# LEDnecklaceW.net
KiCad netlist of a schematic drawn in EAGLE
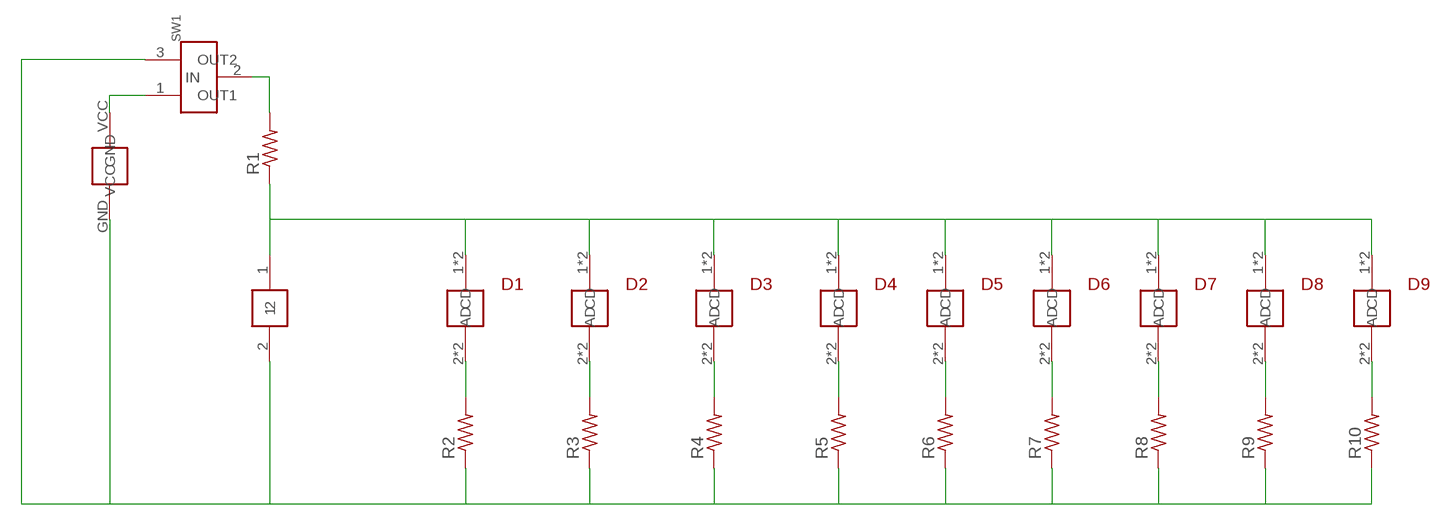
[diagram p0: schematic, sheet 1]

(export (version "E")
  (design (tool "Eeschema 10.0.6"))
  (components
    (comp (ref "D1")
      (value "SZA05A0A")
      (footprint "eagle-import:SZA05A0A")
      (libsource (lib "eagle-import") (part "SZA05A0A"))
    )
    (comp (ref "D2")
      (value "SZA05A0A")
      (footprint "eagle-import:SZA05A0A")
      (libsource (lib "eagle-import") (part "SZA05A0A"))
    )
    (comp (ref "D3")
      (value "SZA05A0A")
      (footprint "eagle-import:SZA05A0A")
      (libsource (lib "eagle-import") (part "SZA05A0A"))
    )
    (comp (ref "D4")
      (value "SZA05A0A")
      (footprint "eagle-import:SZA05A0A")
      (libsource (lib "eagle-import") (part "SZA05A0A"))
    )
    (comp (ref "D5")
      (value "SZA05A0A")
      (footprint "eagle-import:SZA05A0A")
      (libsource (lib "eagle-import") (part "SZA05A0A"))
    )
    (comp (ref "D6")
      (value "SZA05A0A")
      (footprint "eagle-import:SZA05A0A")
      (libsource (lib "eagle-import") (part "SZA05A0A"))
    )
    (comp (ref "D7")
      (value "SZA05A0A")
      (footprint "eagle-import:SZA05A0A")
      (libsource (lib "eagle-import") (part "SZA05A0A"))
    )
    (comp (ref "D8")
      (value "SZA05A0A")
      (footprint "eagle-import:SZA05A0A")
      (libsource (lib "eagle-import") (part "SZA05A0A"))
    )
    (comp (ref "D9")
      (value "SZA05A0A")
      (footprint "eagle-import:SZA05A0A")
      (libsource (lib "eagle-import") (part "SZA05A0A"))
    )
    (comp (ref "P1")
      (value "BU2032SM-BT-GCT")
      (footprint "eagle-import:SMD_BATT_HOLDER_2032")
      (libsource (lib "eagle-import") (part "BU2032SM-BT-GCT"))
    )
    (comp (ref "PC1")
      (value "PDV-P8101")
      (footprint "eagle-import:PHOTOCELL_CERAMIC")
      (libsource (lib "eagle-import") (part "PDV-P8101"))
    )
    (comp (ref "R1")
      (value "R-US_R0603")
      (footprint "eagle-import:R0603")
      (libsource (lib "eagle-import") (part "R-US_R0603"))
    )
    (comp (ref "R2")
      (value "R-US_R0603")
      (footprint "eagle-import:R0603")
      (libsource (lib "eagle-import") (part "R-US_R0603"))
    )
    (comp (ref "R3")
      (value "R-US_R0603")
      (footprint "eagle-import:R0603")
      (libsource (lib "eagle-import") (part "R-US_R0603"))
    )
    (comp (ref "R4")
      (value "R-US_R0603")
      (footprint "eagle-import:R0603")
      (libsource (lib "eagle-import") (part "R-US_R0603"))
    )
    (comp (ref "R5")
      (value "R-US_R0603")
      (footprint "eagle-import:R0603")
      (libsource (lib "eagle-import") (part "R-US_R0603"))
    )
    (comp (ref "R6")
      (value "R-US_R0603")
      (footprint "eagle-import:R0603")
      (libsource (lib "eagle-import") (part "R-US_R0603"))
    )
    (comp (ref "R7")
      (value "R-US_R0603")
      (footprint "eagle-import:R0603")
      (libsource (lib "eagle-import") (part "R-US_R0603"))
    )
    (comp (ref "R8")
      (value "R-US_R0603")
      (footprint "eagle-import:R0603")
      (libsource (lib "eagle-import") (part "R-US_R0603"))
    )
    (comp (ref "R9")
      (value "R-US_R0603")
      (footprint "eagle-import:R0603")
      (libsource (lib "eagle-import") (part "R-US_R0603"))
    )
    (comp (ref "R10")
      (value "R-US_R0603")
      (footprint "eagle-import:R0603")
      (libsource (lib "eagle-import") (part "R-US_R0603"))
    )
    (comp (ref "SW1")
      (value "PCM12SMTR")
      (footprint "eagle-import:PCM12SMTR")
      (libsource (lib "eagle-import") (part "PCM12SMTR"))
    )
  )
  (nets
    (net (code "1") (name "Net-(D1-AD-Pad1)") (class "Default")
      (node (ref "D1") (pin "1") (pinfunction "AD_1") (pintype "bidirectional"))
      (node (ref "D1") (pin "11") (pinfunction "AD_11") (pintype "bidirectional"))
      (node (ref "D2") (pin "1") (pinfunction "AD_1") (pintype "bidirectional"))
      (node (ref "D2") (pin "11") (pinfunction "AD_11") (pintype "bidirectional"))
      (node (ref "D3") (pin "1") (pinfunction "AD_1") (pintype "bidirectional"))
      (node (ref "D3") (pin "11") (pinfunction "AD_11") (pintype "bidirectional"))
      (node (ref "D4") (pin "1") (pinfunction "AD_1") (pintype "bidirectional"))
      (node (ref "D4") (pin "11") (pinfunction "AD_11") (pintype "bidirectional"))
      (node (ref "D5") (pin "1") (pinfunction "AD_1") (pintype "bidirectional"))
      (node (ref "D5") (pin "11") (pinfunction "AD_11") (pintype "bidirectional"))
      (node (ref "D6") (pin "1") (pinfunction "AD_1") (pintype "bidirectional"))
      (node (ref "D6") (pin "11") (pinfunction "AD_11") (pintype "bidirectional"))
      (node (ref "D7") (pin "1") (pinfunction "AD_1") (pintype "bidirectional"))
      (node (ref "D7") (pin "11") (pinfunction "AD_11") (pintype "bidirectional"))
      (node (ref "D8") (pin "1") (pinfunction "AD_1") (pintype "bidirectional"))
      (node (ref "D8") (pin "11") (pinfunction "AD_11") (pintype "bidirectional"))
      (node (ref "D9") (pin "1") (pinfunction "AD_1") (pintype "bidirectional"))
      (node (ref "D9") (pin "11") (pinfunction "AD_11") (pintype "bidirectional"))
      (node (ref "PC1") (pin "1") (pinfunction "1_1") (pintype "bidirectional"))
      (node (ref "R1") (pin "1") (pinfunction "1_1") (pintype "passive"))
    )
    (net (code "2") (name "Net-(D1-CD-Pad12)") (class "Default")
      (node (ref "D1") (pin "12") (pinfunction "CD_12") (pintype "bidirectional"))
      (node (ref "D1") (pin "2") (pinfunction "CD_2") (pintype "bidirectional"))
      (node (ref "R2") (pin "2") (pinfunction "2_2") (pintype "passive"))
    )
    (net (code "3") (name "Net-(D2-CD-Pad12)") (class "Default")
      (node (ref "D2") (pin "12") (pinfunction "CD_12") (pintype "bidirectional"))
      (node (ref "D2") (pin "2") (pinfunction "CD_2") (pintype "bidirectional"))
      (node (ref "R3") (pin "2") (pinfunction "2_2") (pintype "passive"))
    )
    (net (code "4") (name "Net-(D3-CD-Pad12)") (class "Default")
      (node (ref "D3") (pin "12") (pinfunction "CD_12") (pintype "bidirectional"))
      (node (ref "D3") (pin "2") (pinfunction "CD_2") (pintype "bidirectional"))
      (node (ref "R4") (pin "2") (pinfunction "2_2") (pintype "passive"))
    )
    (net (code "5") (name "Net-(D4-CD-Pad12)") (class "Default")
      (node (ref "D4") (pin "12") (pinfunction "CD_12") (pintype "bidirectional"))
      (node (ref "D4") (pin "2") (pinfunction "CD_2") (pintype "bidirectional"))
      (node (ref "R5") (pin "2") (pinfunction "2_2") (pintype "passive"))
    )
    (net (code "6") (name "Net-(D5-CD-Pad12)") (class "Default")
      (node (ref "D5") (pin "12") (pinfunction "CD_12") (pintype "bidirectional"))
      (node (ref "D5") (pin "2") (pinfunction "CD_2") (pintype "bidirectional"))
      (node (ref "R6") (pin "2") (pinfunction "2_2") (pintype "passive"))
    )
    (net (code "7") (name "Net-(D6-CD-Pad12)") (class "Default")
      (node (ref "D6") (pin "12") (pinfunction "CD_12") (pintype "bidirectional"))
      (node (ref "D6") (pin "2") (pinfunction "CD_2") (pintype "bidirectional"))
      (node (ref "R7") (pin "2") (pinfunction "2_2") (pintype "passive"))
    )
    (net (code "8") (name "Net-(D7-CD-Pad12)") (class "Default")
      (node (ref "D7") (pin "12") (pinfunction "CD_12") (pintype "bidirectional"))
      (node (ref "D7") (pin "2") (pinfunction "CD_2") (pintype "bidirectional"))
      (node (ref "R8") (pin "2") (pinfunction "2_2") (pintype "passive"))
    )
    (net (code "9") (name "Net-(D8-CD-Pad12)") (class "Default")
      (node (ref "D8") (pin "12") (pinfunction "CD_12") (pintype "bidirectional"))
      (node (ref "D8") (pin "2") (pinfunction "CD_2") (pintype "bidirectional"))
      (node (ref "R9") (pin "2") (pinfunction "2_2") (pintype "passive"))
    )
    (net (code "10") (name "Net-(D9-CD-Pad12)") (class "Default")
      (node (ref "D9") (pin "12") (pinfunction "CD_12") (pintype "bidirectional"))
      (node (ref "D9") (pin "2") (pinfunction "CD_2") (pintype "bidirectional"))
      (node (ref "R10") (pin "2") (pinfunction "2_2") (pintype "passive"))
    )
    (net (code "11") (name "Net-(SW1-IN)") (class "Default")
      (node (ref "R1") (pin "2") (pinfunction "2_2") (pintype "passive"))
      (node (ref "SW1") (pin "2") (pinfunction "IN_2") (pintype "bidirectional"))
    )
    (net (code "12") (name "Net-(SW1-OUT1)") (class "Default")
      (node (ref "P1") (pin "VCC") (pinfunction "VCC_VCC") (pintype "bidirectional"))
      (node (ref "SW1") (pin "1") (pinfunction "OUT1_1") (pintype "bidirectional"))
    )
    (net (code "13") (name "Net-(SW1-OUT2)") (class "Default")
      (node (ref "P1") (pin "GND") (pinfunction "GND_GND") (pintype "bidirectional"))
      (node (ref "PC1") (pin "2") (pinfunction "2_2") (pintype "bidirectional"))
      (node (ref "R10") (pin "1") (pinfunction "1_1") (pintype "passive"))
      (node (ref "R2") (pin "1") (pinfunction "1_1") (pintype "passive"))
      (node (ref "R3") (pin "1") (pinfunction "1_1") (pintype "passive"))
      (node (ref "R4") (pin "1") (pinfunction "1_1") (pintype "passive"))
      (node (ref "R5") (pin "1") (pinfunction "1_1") (pintype "passive"))
      (node (ref "R6") (pin "1") (pinfunction "1_1") (pintype "passive"))
      (node (ref "R7") (pin "1") (pinfunction "1_1") (pintype "passive"))
      (node (ref "R8") (pin "1") (pinfunction "1_1") (pintype "passive"))
      (node (ref "R9") (pin "1") (pinfunction "1_1") (pintype "passive"))
      (node (ref "SW1") (pin "3") (pinfunction "OUT2_3") (pintype "bidirectional"))
    )
  )
)
